# ACtoDCconvtr.net
KiCad netlist of a schematic drawn in EAGLE
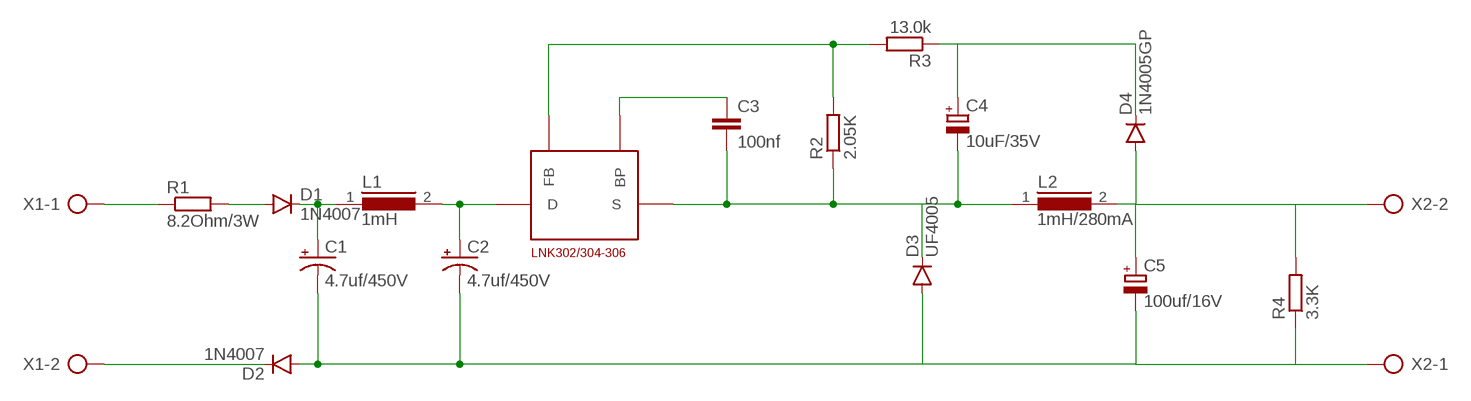
[diagram p0: schematic, sheet 1]

(export (version "E")
  (design (tool "Eeschema 10.0.6"))
  (components
    (comp (ref "C1")
      (value "4.7uf/450V")
      (footprint "eagle-import:CPOL-RADIAL-1000UF-25V-KIT")
      (libsource (lib "eagle-import") (part "1000UF-25V(PTH)KIT"))
    )
    (comp (ref "C2")
      (value "4.7uf/450V")
      (footprint "eagle-import:CPOL-RADIAL-1000UF-25V-KIT")
      (libsource (lib "eagle-import") (part "1000UF-25V(PTH)KIT"))
    )
    (comp (ref "C3")
      (value "100nf")
      (footprint "eagle-import:C2.5-4")
      (libsource (lib "eagle-import") (part "C2.5/4"))
    )
    (comp (ref "C4")
      (value "10uF/35V")
      (footprint "eagle-import:E2,5-5")
      (libsource (lib "eagle-import") (part "CPOL-EUE2.5-5"))
    )
    (comp (ref "C5")
      (value "100uf/16V")
      (footprint "eagle-import:E2,5-7")
      (libsource (lib "eagle-import") (part "CPOL-EUE2.5-7"))
    )
    (comp (ref "D1")
      (value "1N4007")
      (footprint "eagle-import:DIODE-1N4148-KIT")
      (libsource (lib "eagle-import") (part "DIODEKIT"))
    )
    (comp (ref "D2")
      (value "1N4007")
      (footprint "eagle-import:DIODE-1N4148-KIT")
      (libsource (lib "eagle-import") (part "DIODEKIT"))
    )
    (comp (ref "D3")
      (value "UF4005")
      (footprint "eagle-import:DIODE-1N4148-KIT")
      (libsource (lib "eagle-import") (part "DIODEKIT"))
    )
    (comp (ref "D4")
      (value "1N4005GP")
      (footprint "eagle-import:DIODE-1N4148-KIT")
      (libsource (lib "eagle-import") (part "DIODEKIT"))
    )
    (comp (ref "L1")
      (value "1mH")
      (footprint "eagle-import:82114R")
      (libsource (lib "eagle-import") (part "82114R"))
    )
    (comp (ref "L2")
      (value "1mH/280mA")
      (footprint "eagle-import:82114R")
      (libsource (lib "eagle-import") (part "82114R"))
    )
    (comp (ref "R1")
      (value "8.2Ohm/3W")
      (footprint "eagle-import:0411_15")
      (libsource (lib "eagle-import") (part "R-EU_0411/15"))
    )
    (comp (ref "R2")
      (value "2.05K")
      (footprint "eagle-import:0207_2V")
      (libsource (lib "eagle-import") (part "R-EU_0207/2V"))
    )
    (comp (ref "R3")
      (value "13.0k")
      (footprint "eagle-import:0207_2V")
      (libsource (lib "eagle-import") (part "R-EU_0207/2V"))
    )
    (comp (ref "R4")
      (value "3.3K")
      (footprint "eagle-import:0207_10")
      (libsource (lib "eagle-import") (part "R-EU_0207/10"))
    )
    (comp (ref "U$1")
      (value "LNK302/304-306")
      (footprint "eagle-import:SMD-8B")
      (libsource (lib "eagle-import") (part "LNK302/304-306"))
    )
    (comp (ref "X1")
      (value "AK300/2")
      (footprint "eagle-import:AK300_2")
      (libsource (lib "eagle-import") (part "AK300/2"))
    )
    (comp (ref "X2")
      (value "AK300/2")
      (footprint "eagle-import:AK300_2")
      (libsource (lib "eagle-import") (part "AK300/2"))
    )
  )
  (nets
    (net (code "1") (name "Net-(C1-Pad+)") (class "Default")
      (node (ref "C1") (pin "+") (pinfunction "+_+") (pintype "passive"))
      (node (ref "D1") (pin "C") (pinfunction "C_C") (pintype "passive"))
      (node (ref "L1") (pin "1") (pinfunction "1_1") (pintype "passive"))
    )
    (net (code "2") (name "Net-(C2-Pad+)") (class "Default")
      (node (ref "C2") (pin "+") (pinfunction "+_+") (pintype "passive"))
      (node (ref "L1") (pin "2") (pinfunction "2_2") (pintype "passive"))
      (node (ref "U$1") (pin "D") (pinfunction "D_D") (pintype "bidirectional"))
    )
    (net (code "3") (name "Net-(C3-Pad1)") (class "Default")
      (node (ref "C3") (pin "1") (pinfunction "1_1") (pintype "passive"))
      (node (ref "U$1") (pin "BP") (pinfunction "BP_BP") (pintype "bidirectional"))
    )
    (net (code "4") (name "Net-(C4-Pad+)") (class "Default")
      (node (ref "C4") (pin "+") (pinfunction "+_+") (pintype "passive"))
      (node (ref "D4") (pin "C") (pinfunction "C_C") (pintype "passive"))
      (node (ref "R3") (pin "1") (pinfunction "1_1") (pintype "passive"))
    )
    (net (code "5") (name "Net-(D1-PadA)") (class "Default")
      (node (ref "D1") (pin "A") (pinfunction "A_A") (pintype "passive"))
      (node (ref "R1") (pin "2") (pinfunction "2_2") (pintype "passive"))
    )
    (net (code "6") (name "Net-(R2-Pad2)") (class "Default")
      (node (ref "R2") (pin "2") (pinfunction "2_2") (pintype "passive"))
      (node (ref "R3") (pin "2") (pinfunction "2_2") (pintype "passive"))
      (node (ref "U$1") (pin "FB") (pinfunction "FB_FB") (pintype "bidirectional"))
    )
    (net (code "7") (name "Net-(U$1-S)") (class "Default")
      (node (ref "C3") (pin "2") (pinfunction "2_2") (pintype "passive"))
      (node (ref "C4") (pin "-") (pinfunction "-_-") (pintype "passive"))
      (node (ref "D3") (pin "C") (pinfunction "C_C") (pintype "passive"))
      (node (ref "L2") (pin "1") (pinfunction "1_1") (pintype "passive"))
      (node (ref "R2") (pin "1") (pinfunction "1_1") (pintype "passive"))
      (node (ref "U$1") (pin "S1") (pinfunction "S_S1") (pintype "bidirectional"))
    )
    (net (code "8") (name "Net-(X1A-KL)") (class "Default")
      (node (ref "R1") (pin "1") (pinfunction "1_1") (pintype "passive"))
      (node (ref "X1") (pin "1") (pinfunction "KL_1") (pintype "passive"))
    )
    (net (code "9") (name "Net-(X1B-KL)") (class "Default")
      (node (ref "D2") (pin "C") (pinfunction "C_C") (pintype "passive"))
      (node (ref "X1") (pin "2") (pinfunction "KL_2") (pintype "passive"))
    )
    (net (code "10") (name "Net-(X2A-KL)") (class "Default")
      (node (ref "C1") (pin "-") (pinfunction "-_-") (pintype "passive"))
      (node (ref "C2") (pin "-") (pinfunction "-_-") (pintype "passive"))
      (node (ref "C5") (pin "-") (pinfunction "-_-") (pintype "passive"))
      (node (ref "D2") (pin "A") (pinfunction "A_A") (pintype "passive"))
      (node (ref "D3") (pin "A") (pinfunction "A_A") (pintype "passive"))
      (node (ref "R4") (pin "1") (pinfunction "1_1") (pintype "passive"))
      (node (ref "X2") (pin "1") (pinfunction "KL_1") (pintype "passive"))
    )
    (net (code "11") (name "Net-(X2B-KL)") (class "Default")
      (node (ref "C5") (pin "+") (pinfunction "+_+") (pintype "passive"))
      (node (ref "D4") (pin "A") (pinfunction "A_A") (pintype "passive"))
      (node (ref "L2") (pin "2") (pinfunction "2_2") (pintype "passive"))
      (node (ref "R4") (pin "2") (pinfunction "2_2") (pintype "passive"))
      (node (ref "X2") (pin "2") (pinfunction "KL_2") (pintype "passive"))
    )
  )
)
